# WeighingControl_Karbra.net
KiCad netlist of a schematic drawn in EAGLE
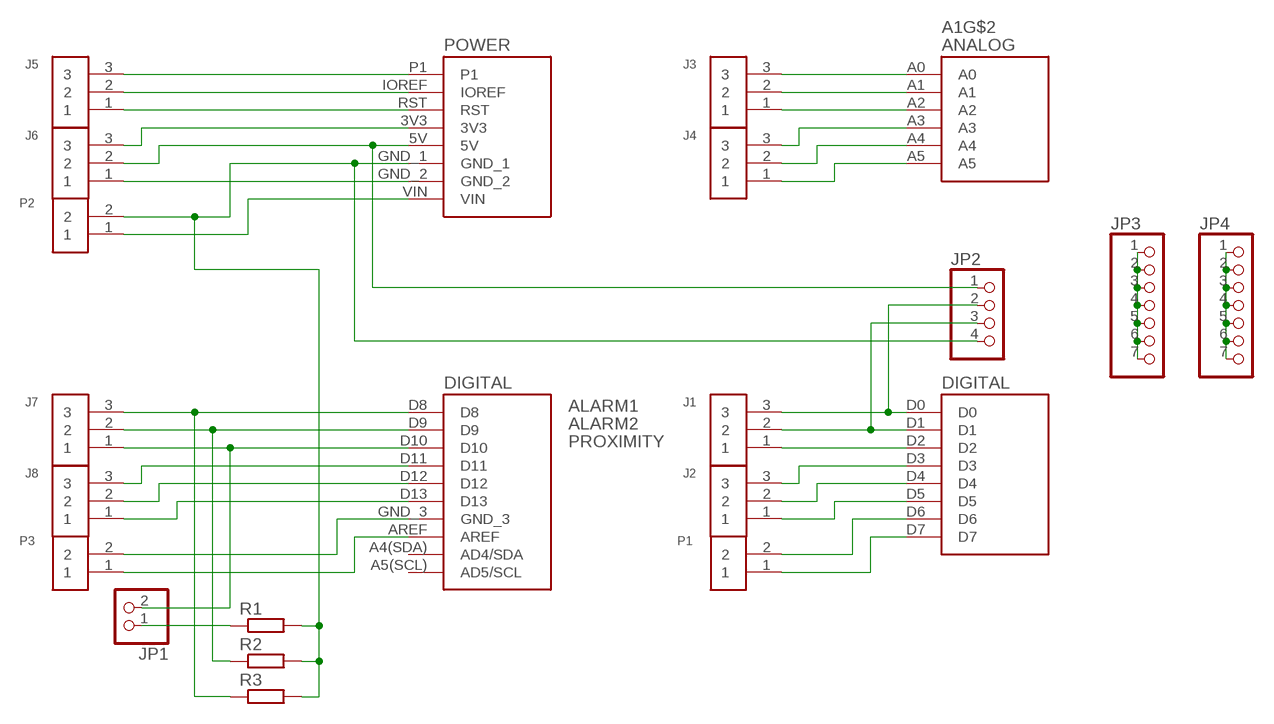
[diagram p0: schematic, sheet 1]

(export (version "E")
  (design (tool "Eeschema 10.0.6"))
  (components
    (comp (ref "A1")
      (value "A000066")
      (footprint "eagle-import:ARDUINO_A000066")
      (fields (field (name "DIGI-KEY_PART_NUMBER") "1050-1024-ND") (field (name "MF") "Arduino"))
      (libsource (lib "eagle-import") (part "A000066"))
    )
    (comp (ref "J1")
      (value "282837-3")
      (footprint "eagle-import:TE_282837-3")
      (fields (field (name "MF") "TE Connectivity"))
      (libsource (lib "eagle-import") (part "282837-3"))
    )
    (comp (ref "J2")
      (value "282837-3")
      (footprint "eagle-import:TE_282837-3")
      (fields (field (name "MF") "TE Connectivity"))
      (libsource (lib "eagle-import") (part "282837-3"))
    )
    (comp (ref "J3")
      (value "282837-3")
      (footprint "eagle-import:TE_282837-3")
      (fields (field (name "MF") "TE Connectivity"))
      (libsource (lib "eagle-import") (part "282837-3"))
    )
    (comp (ref "J4")
      (value "282837-3")
      (footprint "eagle-import:TE_282837-3")
      (fields (field (name "MF") "TE Connectivity"))
      (libsource (lib "eagle-import") (part "282837-3"))
    )
    (comp (ref "J5")
      (value "282837-3")
      (footprint "eagle-import:TE_282837-3")
      (fields (field (name "MF") "TE Connectivity"))
      (libsource (lib "eagle-import") (part "282837-3"))
    )
    (comp (ref "J6")
      (value "282837-3")
      (footprint "eagle-import:TE_282837-3")
      (fields (field (name "MF") "TE Connectivity"))
      (libsource (lib "eagle-import") (part "282837-3"))
    )
    (comp (ref "J7")
      (value "282837-3")
      (footprint "eagle-import:TE_282837-3")
      (fields (field (name "MF") "TE Connectivity"))
      (libsource (lib "eagle-import") (part "282837-3"))
    )
    (comp (ref "J8")
      (value "282837-3")
      (footprint "eagle-import:TE_282837-3")
      (fields (field (name "MF") "TE Connectivity"))
      (libsource (lib "eagle-import") (part "282837-3"))
    )
    (comp (ref "JP1")
      (value "PINHD-1X2")
      (footprint "eagle-import:1X02")
      (libsource (lib "eagle-import") (part "PINHD-1X2"))
    )
    (comp (ref "JP2")
      (value "PINHD-1X4")
      (footprint "eagle-import:1X04")
      (libsource (lib "eagle-import") (part "PINHD-1X4"))
    )
    (comp (ref "JP3")
      (value "PINHD-1X7")
      (footprint "eagle-import:1X07")
      (libsource (lib "eagle-import") (part "PINHD-1X7"))
    )
    (comp (ref "JP4")
      (value "PINHD-1X7")
      (footprint "eagle-import:1X07")
      (libsource (lib "eagle-import") (part "PINHD-1X7"))
    )
    (comp (ref "P1")
      (value "282837-2")
      (footprint "eagle-import:TE_282837-2")
      (fields (field (name "MF") "TE Connectivity"))
      (libsource (lib "eagle-import") (part "282837-2"))
    )
    (comp (ref "P2")
      (value "282837-2")
      (footprint "eagle-import:TE_282837-2")
      (fields (field (name "MF") "TE Connectivity"))
      (libsource (lib "eagle-import") (part "282837-2"))
    )
    (comp (ref "P3")
      (value "282837-2")
      (footprint "eagle-import:TE_282837-2")
      (fields (field (name "MF") "TE Connectivity"))
      (libsource (lib "eagle-import") (part "282837-2"))
    )
    (comp (ref "R1")
      (value "R-EU_0204/7")
      (footprint "eagle-import:0204_7")
      (libsource (lib "eagle-import") (part "R-EU_0204/7"))
    )
    (comp (ref "R2")
      (value "R-EU_0204/7")
      (footprint "eagle-import:0204_7")
      (libsource (lib "eagle-import") (part "R-EU_0204/7"))
    )
    (comp (ref "R3")
      (value "R-EU_0204/7")
      (footprint "eagle-import:0204_7")
      (libsource (lib "eagle-import") (part "R-EU_0204/7"))
    )
  )
  (nets
    (net (code "1") (name "Net-(A1-Pad3V3)") (class "Default")
      (node (ref "A1") (pin "3V3") (pinfunction "3V3_3V3") (pintype "power_in"))
      (node (ref "J6") (pin "3") (pinfunction "3_3") (pintype "passive"))
    )
    (net (code "2") (name "Net-(A1-Pad5V)") (class "Default")
      (node (ref "A1") (pin "5V") (pinfunction "5V_5V") (pintype "power_in"))
      (node (ref "J6") (pin "2") (pinfunction "2_2") (pintype "passive"))
      (node (ref "JP2") (pin "1") (pinfunction "1_1") (pintype "passive"))
    )
    (net (code "3") (name "Net-(A1-PadA0)") (class "Default")
      (node (ref "A1") (pin "A0") (pinfunction "A0_A0") (pintype "bidirectional"))
      (node (ref "J3") (pin "3") (pinfunction "3_3") (pintype "passive"))
    )
    (net (code "4") (name "Net-(A1-PadA1)") (class "Default")
      (node (ref "A1") (pin "A1") (pinfunction "A1_A1") (pintype "bidirectional"))
      (node (ref "J3") (pin "2") (pinfunction "2_2") (pintype "passive"))
    )
    (net (code "5") (name "Net-(A1-PadA2)") (class "Default")
      (node (ref "A1") (pin "A2") (pinfunction "A2_A2") (pintype "bidirectional"))
      (node (ref "J3") (pin "1") (pinfunction "1_1") (pintype "passive"))
    )
    (net (code "6") (name "Net-(A1-PadA3)") (class "Default")
      (node (ref "A1") (pin "A3") (pinfunction "A3_A3") (pintype "bidirectional"))
      (node (ref "J4") (pin "3") (pinfunction "3_3") (pintype "passive"))
    )
    (net (code "7") (name "Net-(A1-PadA4)") (class "Default")
      (node (ref "A1") (pin "A4") (pinfunction "A4_A4") (pintype "bidirectional"))
      (node (ref "J4") (pin "2") (pinfunction "2_2") (pintype "passive"))
    )
    (net (code "8") (name "Net-(A1-PadA5)") (class "Default")
      (node (ref "A1") (pin "A5") (pinfunction "A5_A5") (pintype "bidirectional"))
      (node (ref "J4") (pin "1") (pinfunction "1_1") (pintype "passive"))
    )
    (net (code "9") (name "Net-(A1-PadAREF)") (class "Default")
      (node (ref "A1") (pin "AREF") (pinfunction "AREF_AREF") (pintype "bidirectional"))
      (node (ref "P3") (pin "1") (pinfunction "1_1") (pintype "passive"))
    )
    (net (code "10") (name "Net-(A1-PadD0)") (class "Default")
      (node (ref "A1") (pin "D0") (pinfunction "D0_D0") (pintype "bidirectional"))
      (node (ref "J1") (pin "3") (pinfunction "3_3") (pintype "passive"))
      (node (ref "JP2") (pin "2") (pinfunction "2_2") (pintype "passive"))
    )
    (net (code "11") (name "Net-(A1-PadD1)") (class "Default")
      (node (ref "A1") (pin "D1") (pinfunction "D1_D1") (pintype "bidirectional"))
      (node (ref "J1") (pin "2") (pinfunction "2_2") (pintype "passive"))
      (node (ref "JP2") (pin "3") (pinfunction "3_3") (pintype "passive"))
    )
    (net (code "12") (name "Net-(A1-PadD2)") (class "Default")
      (node (ref "A1") (pin "D2") (pinfunction "D2_D2") (pintype "bidirectional"))
      (node (ref "J1") (pin "1") (pinfunction "1_1") (pintype "passive"))
    )
    (net (code "13") (name "Net-(A1-PadD3)") (class "Default")
      (node (ref "A1") (pin "D3") (pinfunction "D3_D3") (pintype "bidirectional"))
      (node (ref "J2") (pin "3") (pinfunction "3_3") (pintype "passive"))
    )
    (net (code "14") (name "Net-(A1-PadD4)") (class "Default")
      (node (ref "A1") (pin "D4") (pinfunction "D4_D4") (pintype "bidirectional"))
      (node (ref "J2") (pin "2") (pinfunction "2_2") (pintype "passive"))
    )
    (net (code "15") (name "Net-(A1-PadD5)") (class "Default")
      (node (ref "A1") (pin "D5") (pinfunction "D5_D5") (pintype "bidirectional"))
      (node (ref "J2") (pin "1") (pinfunction "1_1") (pintype "passive"))
    )
    (net (code "16") (name "Net-(A1-PadD6)") (class "Default")
      (node (ref "A1") (pin "D6") (pinfunction "D6_D6") (pintype "bidirectional"))
      (node (ref "P1") (pin "2") (pinfunction "2_2") (pintype "passive"))
    )
    (net (code "17") (name "Net-(A1-PadD7)") (class "Default")
      (node (ref "A1") (pin "D7") (pinfunction "D7_D7") (pintype "bidirectional"))
      (node (ref "P1") (pin "1") (pinfunction "1_1") (pintype "passive"))
    )
    (net (code "18") (name "Net-(A1-PadD8)") (class "Default")
      (node (ref "A1") (pin "D8") (pinfunction "D8_D8") (pintype "bidirectional"))
      (node (ref "J7") (pin "3") (pinfunction "3_3") (pintype "passive"))
      (node (ref "R3") (pin "1") (pinfunction "1_1") (pintype "passive"))
    )
    (net (code "19") (name "Net-(A1-PadD9)") (class "Default")
      (node (ref "A1") (pin "D9") (pinfunction "D9_D9") (pintype "bidirectional"))
      (node (ref "J7") (pin "2") (pinfunction "2_2") (pintype "passive"))
      (node (ref "R2") (pin "1") (pinfunction "1_1") (pintype "passive"))
    )
    (net (code "20") (name "Net-(A1-PadD10)") (class "Default")
      (node (ref "A1") (pin "D10") (pinfunction "D10_D10") (pintype "bidirectional"))
      (node (ref "J7") (pin "1") (pinfunction "1_1") (pintype "passive"))
      (node (ref "JP1") (pin "2") (pinfunction "2_2") (pintype "passive"))
    )
    (net (code "21") (name "Net-(A1-PadD11)") (class "Default")
      (node (ref "A1") (pin "D11") (pinfunction "D11_D11") (pintype "bidirectional"))
      (node (ref "J8") (pin "3") (pinfunction "3_3") (pintype "passive"))
    )
    (net (code "22") (name "Net-(A1-PadD12)") (class "Default")
      (node (ref "A1") (pin "D12") (pinfunction "D12_D12") (pintype "bidirectional"))
      (node (ref "J8") (pin "2") (pinfunction "2_2") (pintype "passive"))
    )
    (net (code "23") (name "Net-(A1-PadD13)") (class "Default")
      (node (ref "A1") (pin "D13") (pinfunction "D13_D13") (pintype "bidirectional"))
      (node (ref "J8") (pin "1") (pinfunction "1_1") (pintype "passive"))
    )
    (net (code "24") (name "Net-(A1-PadGND_1)") (class "Default")
      (node (ref "A1") (pin "GND_1") (pinfunction "GND_1_GND_1") (pintype "power_in"))
      (node (ref "JP2") (pin "4") (pinfunction "4_4") (pintype "passive"))
      (node (ref "P2") (pin "2") (pinfunction "2_2") (pintype "passive"))
      (node (ref "R1") (pin "2") (pinfunction "2_2") (pintype "passive"))
      (node (ref "R2") (pin "2") (pinfunction "2_2") (pintype "passive"))
      (node (ref "R3") (pin "2") (pinfunction "2_2") (pintype "passive"))
    )
    (net (code "25") (name "Net-(A1-PadGND_2)") (class "Default")
      (node (ref "A1") (pin "GND_2") (pinfunction "GND_2_GND_2") (pintype "power_in"))
      (node (ref "J6") (pin "1") (pinfunction "1_1") (pintype "passive"))
    )
    (net (code "26") (name "Net-(A1-PadGND_3)") (class "Default")
      (node (ref "A1") (pin "GND_3") (pinfunction "GND_3_GND_3") (pintype "power_in"))
      (node (ref "P3") (pin "2") (pinfunction "2_2") (pintype "passive"))
    )
    (net (code "27") (name "Net-(A1-PadIOREF)") (class "Default")
      (node (ref "A1") (pin "IOREF") (pinfunction "IOREF_IOREF") (pintype "bidirectional"))
      (node (ref "J5") (pin "2") (pinfunction "2_2") (pintype "passive"))
    )
    (net (code "28") (name "Net-(A1-PadP1)") (class "Default")
      (node (ref "A1") (pin "P1") (pinfunction "P1_P1") (pintype "bidirectional"))
      (node (ref "J5") (pin "3") (pinfunction "3_3") (pintype "passive"))
    )
    (net (code "29") (name "Net-(A1-PadRST)") (class "Default")
      (node (ref "A1") (pin "RST") (pinfunction "RST_RST") (pintype "bidirectional"))
      (node (ref "J5") (pin "1") (pinfunction "1_1") (pintype "passive"))
    )
    (net (code "30") (name "Net-(A1-PadVIN)") (class "Default")
      (node (ref "A1") (pin "VIN") (pinfunction "VIN_VIN") (pintype "power_in"))
      (node (ref "P2") (pin "1") (pinfunction "1_1") (pintype "passive"))
    )
    (net (code "31") (name "Net-(JP1-Pad1)") (class "Default")
      (node (ref "JP1") (pin "1") (pinfunction "1_1") (pintype "passive"))
      (node (ref "R1") (pin "1") (pinfunction "1_1") (pintype "passive"))
    )
    (net (code "32") (name "Net-(JP3-Pad1)") (class "Default")
      (node (ref "JP3") (pin "1") (pinfunction "1_1") (pintype "passive"))
      (node (ref "JP3") (pin "2") (pinfunction "2_2") (pintype "passive"))
      (node (ref "JP3") (pin "3") (pinfunction "3_3") (pintype "passive"))
      (node (ref "JP3") (pin "4") (pinfunction "4_4") (pintype "passive"))
      (node (ref "JP3") (pin "5") (pinfunction "5_5") (pintype "passive"))
      (node (ref "JP3") (pin "6") (pinfunction "6_6") (pintype "passive"))
      (node (ref "JP3") (pin "7") (pinfunction "7_7") (pintype "passive"))
    )
    (net (code "33") (name "Net-(JP4-Pad1)") (class "Default")
      (node (ref "JP4") (pin "1") (pinfunction "1_1") (pintype "passive"))
      (node (ref "JP4") (pin "2") (pinfunction "2_2") (pintype "passive"))
      (node (ref "JP4") (pin "3") (pinfunction "3_3") (pintype "passive"))
      (node (ref "JP4") (pin "4") (pinfunction "4_4") (pintype "passive"))
      (node (ref "JP4") (pin "5") (pinfunction "5_5") (pintype "passive"))
      (node (ref "JP4") (pin "6") (pinfunction "6_6") (pintype "passive"))
      (node (ref "JP4") (pin "7") (pinfunction "7_7") (pintype "passive"))
    )
    (net (code "34") (name "unconnected-(A1D-AD4{slash}SDA-PadA4(SDA))") (class "Default")
      (node (ref "A1") (pin "A4(SDA)") (pinfunction "AD4/SDA_A4(SDA)") (pintype "bidirectional"))
    )
    (net (code "35") (name "unconnected-(A1D-AD5{slash}SCL-PadA5(SCL))") (class "Default")
      (node (ref "A1") (pin "A5(SCL)") (pinfunction "AD5/SCL_A5(SCL)") (pintype "bidirectional"))
    )
  )
)
